# Top.net
KiCad netlist of a schematic drawn in Altium Designer
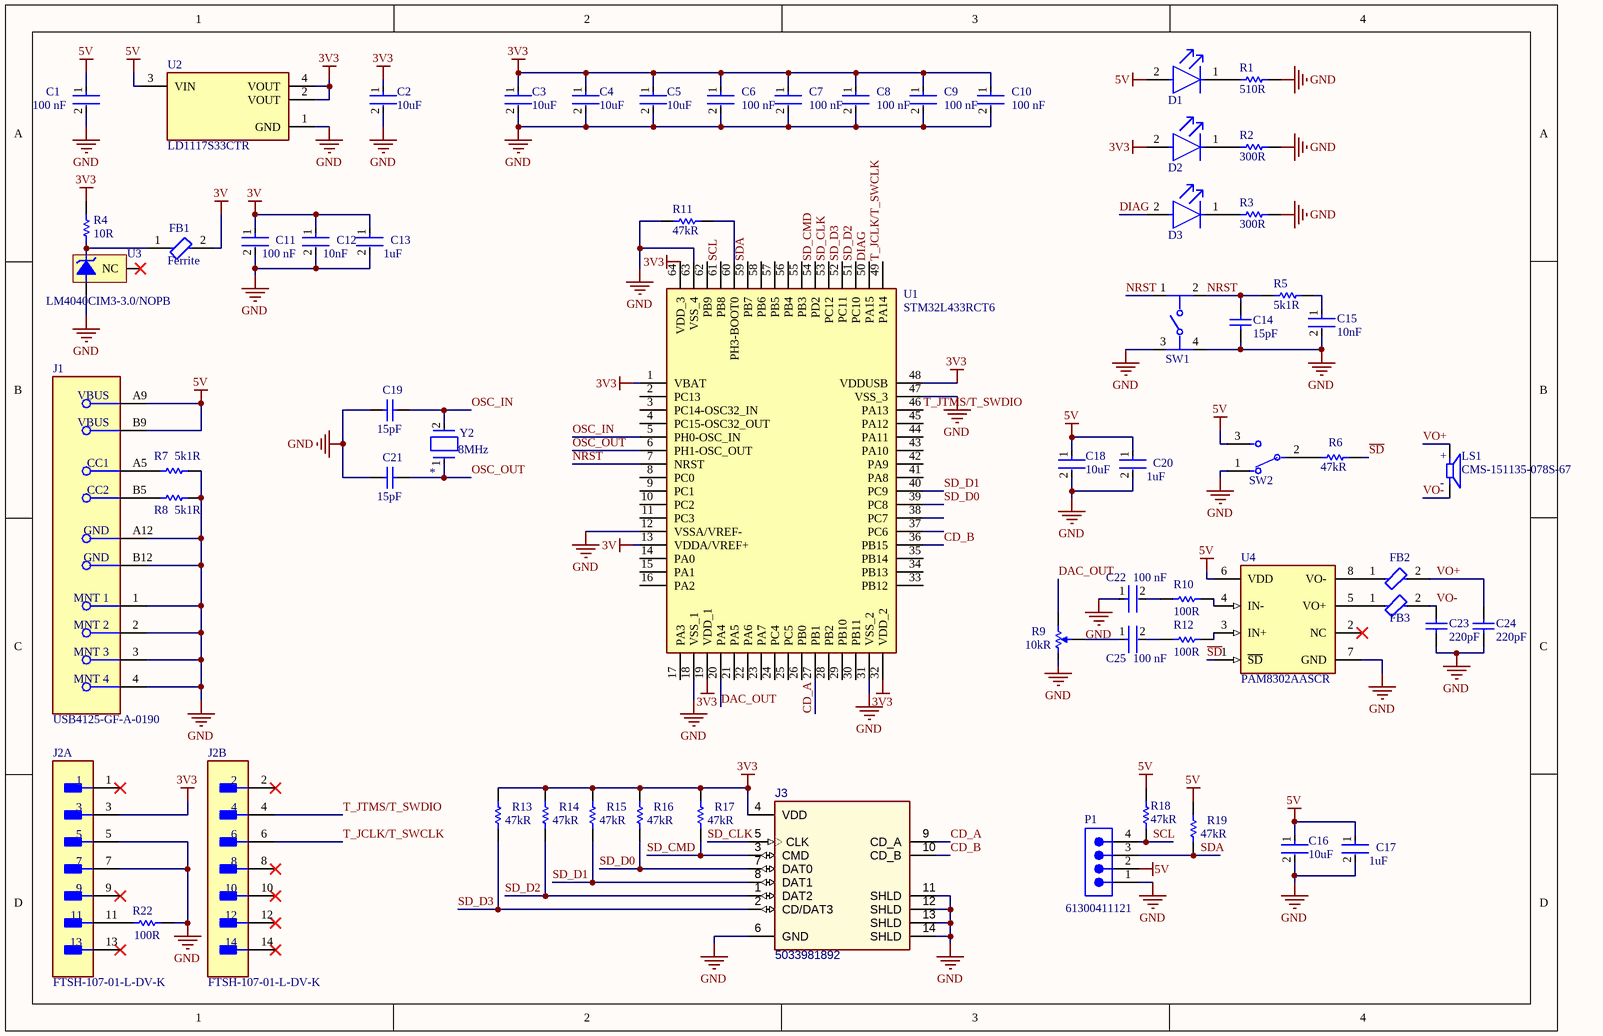
[diagram p0: Top.SchDoc]

(export (version "E")
  (design (tool "Eeschema 10.0.6"))
  (components
    (comp (ref "C1")
      (value "100 nF")
      (footprint "FP-CC0805-0_85-MFG")
      (description "CAP CER 0.1UF 16V X7R 0805")
      (fields
        (field (name "MANUFACTURER PART NUMBER") "CC0805KRX7R7BB104")
        (field (name "MANUFACTURER") "Yageo")
      )
      (libsource (lib "Altium Content Vault") (part "11868f565c42a9108669ba33697ecf6"))
    )
    (comp (ref "C2")
      (value "10uF")
      (footprint "FP-C0805C-DG-MFG")
      (description "CAP CER 10UF 10V X5R 0805")
      (fields (field (name "TOLERANCE") "10%") (field (name "MANUFACTURER PART NUMBER") "C0805C106K8PACTU"))
      (libsource (lib "Altium Content Vault") (part "11868f565c42a9108669ba33697ecf6"))
    )
    (comp (ref "C3")
      (value "10uF")
      (footprint "FP-C0805C-DG-MFG")
      (description "CAP CER 10UF 10V X5R 0805")
      (fields (field (name "TOLERANCE") "10%") (field (name "MANUFACTURER PART NUMBER") "C0805C106K8PACTU"))
      (libsource (lib "Altium Content Vault") (part "11868f565c42a9108669ba33697ecf6"))
    )
    (comp (ref "C4")
      (value "10uF")
      (footprint "FP-C0805C-DG-MFG")
      (description "CAP CER 10UF 10V X5R 0805")
      (fields (field (name "TOLERANCE") "10%") (field (name "MANUFACTURER PART NUMBER") "C0805C106K8PACTU"))
      (libsource (lib "Altium Content Vault") (part "11868f565c42a9108669ba33697ecf6"))
    )
    (comp (ref "C5")
      (value "10uF")
      (footprint "FP-C0805C-DG-MFG")
      (description "CAP CER 10UF 10V X5R 0805")
      (fields (field (name "TOLERANCE") "10%") (field (name "MANUFACTURER PART NUMBER") "C0805C106K8PACTU"))
      (libsource (lib "Altium Content Vault") (part "11868f565c42a9108669ba33697ecf6"))
    )
    (comp (ref "C6")
      (value "100 nF")
      (footprint "FP-CC0805-0_85-MFG")
      (description "CAP CER 0.1UF 16V X7R 0805")
      (fields
        (field (name "MANUFACTURER PART NUMBER") "CC0805KRX7R7BB104")
        (field (name "MANUFACTURER") "Yageo")
      )
      (libsource (lib "Altium Content Vault") (part "11868f565c42a9108669ba33697ecf6"))
    )
    (comp (ref "C7")
      (value "100 nF")
      (footprint "FP-CC0805-0_85-MFG")
      (description "CAP CER 0.1UF 16V X7R 0805")
      (fields
        (field (name "MANUFACTURER PART NUMBER") "CC0805KRX7R7BB104")
        (field (name "MANUFACTURER") "Yageo")
      )
      (libsource (lib "Altium Content Vault") (part "11868f565c42a9108669ba33697ecf6"))
    )
    (comp (ref "C8")
      (value "100 nF")
      (footprint "FP-CC0805-0_85-MFG")
      (description "CAP CER 0.1UF 16V X7R 0805")
      (fields
        (field (name "MANUFACTURER PART NUMBER") "CC0805KRX7R7BB104")
        (field (name "MANUFACTURER") "Yageo")
      )
      (libsource (lib "Altium Content Vault") (part "11868f565c42a9108669ba33697ecf6"))
    )
    (comp (ref "C9")
      (value "100 nF")
      (footprint "FP-CC0805-0_85-MFG")
      (description "CAP CER 0.1UF 16V X7R 0805")
      (fields
        (field (name "MANUFACTURER PART NUMBER") "CC0805KRX7R7BB104")
        (field (name "MANUFACTURER") "Yageo")
      )
      (libsource (lib "Altium Content Vault") (part "11868f565c42a9108669ba33697ecf6"))
    )
    (comp (ref "C10")
      (value "CC0805KRX7R7BB104")
      (footprint "FP-CC0805-0_85-MFG")
      (description "CAP CER 0.1UF 16V X7R 0805")
      (fields
        (field (name "MANUFACTURER") "Yageo")
        (field (name "OCTOPART") "https://octopart.com/cc0805krx7r7bb104-yageo-39467769")
        (field (name "CAPACITANCE") "100 nF")
      )
      (libsource (lib "Altium Content Vault") (part "11868f565c42a9108669ba33697ecf6"))
    )
    (comp (ref "C11")
      (value "C0805C103K2RACTU")
      (footprint "FP-C0805C-DN-MFG")
      (description "CAP CER 10000PF 200V X7R 0805")
      (fields
        (field (name "OCTOPART") "https://octopart.com/c0805c103k2ractu-kemet-9138347")
        (field (name "CAPACITANCE") "10nF")
        (field (name "TOLERANCE") "0.1")
      )
      (libsource (lib "Altium Content Vault") (part "b4654b650e69147ec39a6b967a45e02"))
    )
    (comp (ref "C12")
      (value "100 nF")
      (footprint "FP-CC0805-0_85-MFG")
      (description "CAP CER 0.1UF 16V X7R 0805")
      (fields
        (field (name "MANUFACTURER PART NUMBER") "CC0805KRX7R7BB104")
        (field (name "MANUFACTURER") "Yageo")
      )
      (libsource (lib "Altium Content Vault") (part "11868f565c42a9108669ba33697ecf6"))
    )
    (comp (ref "C13")
      (value "C2012X5R1E105K125AA")
      (footprint "FP-C2012-125-0_2-IPC_A")
      (description "Multilayer Ceramic Capacitors 1μF ±10% 25V X5R SMD 0805")
      (fields
        (field (name "VOLTAGE") "25V")
        (field (name "CAPACITANCE") "1uF")
        (field (name "TOLERANCE") "10%")
      )
      (libsource (lib "Altium Content Vault") (part "b4654b650e69147ec39a6b967a45e02"))
    )
    (comp (ref "C14")
      (value "15pF")
      (footprint "CAPC1508X91X25LL25T13")
      (fields
        (field (name "MANUFACTURER") "AVX Interconnect / Elco")
        (field (name "PART NUMBER") "06032U150GAT2A")
      )
      (libsource (lib "Altium Content Vault") (part "CAP"))
    )
    (comp (ref "C15")
      (value "C0805C103K2RACTU")
      (footprint "FP-C0805C-DN-MFG")
      (description "CAP CER 10000PF 200V X7R 0805")
      (fields
        (field (name "OCTOPART") "https://octopart.com/c0805c103k2ractu-kemet-9138347")
        (field (name "CAPACITANCE") "10nF")
        (field (name "TOLERANCE") "0.1")
      )
      (libsource (lib "Altium Content Vault") (part "b4654b650e69147ec39a6b967a45e02"))
    )
    (comp (ref "C16")
      (value "10uF")
      (footprint "FP-C0805C-DG-MFG")
      (description "CAP CER 10UF 10V X5R 0805")
      (fields (field (name "TOLERANCE") "10%") (field (name "MANUFACTURER PART NUMBER") "C0805C106K8PACTU"))
      (libsource (lib "Altium Content Vault") (part "11868f565c42a9108669ba33697ecf6"))
    )
    (comp (ref "C17")
      (value "C2012X5R1E105K125AA")
      (footprint "FP-C2012-125-0_2-IPC_A")
      (description "Multilayer Ceramic Capacitors 1μF ±10% 25V X5R SMD 0805")
      (fields
        (field (name "VOLTAGE") "25V")
        (field (name "CAPACITANCE") "1uF")
        (field (name "TOLERANCE") "10%")
      )
      (libsource (lib "Altium Content Vault") (part "b4654b650e69147ec39a6b967a45e02"))
    )
    (comp (ref "C18")
      (value "10uF")
      (footprint "FP-C0805C-DG-MFG")
      (description "CAP CER 10UF 10V X5R 0805")
      (fields (field (name "TOLERANCE") "10%") (field (name "MANUFACTURER PART NUMBER") "C0805C106K8PACTU"))
      (libsource (lib "Altium Content Vault") (part "11868f565c42a9108669ba33697ecf6"))
    )
    (comp (ref "C19")
      (value "15pF")
      (footprint "CAPC1508X91X25LL25T13")
      (fields
        (field (name "MANUFACTURER") "AVX Interconnect / Elco")
        (field (name "PART NUMBER") "06032U150GAT2A")
      )
      (libsource (lib "Altium Content Vault") (part "CAP"))
    )
    (comp (ref "C20")
      (value "C2012X5R1E105K125AA")
      (footprint "FP-C2012-125-0_2-IPC_A")
      (description "Multilayer Ceramic Capacitors 1μF ±10% 25V X5R SMD 0805")
      (fields
        (field (name "VOLTAGE") "25V")
        (field (name "CAPACITANCE") "1uF")
        (field (name "TOLERANCE") "10%")
      )
      (libsource (lib "Altium Content Vault") (part "b4654b650e69147ec39a6b967a45e02"))
    )
    (comp (ref "C21")
      (value "15pF")
      (footprint "CAPC1508X91X25LL25T13")
      (fields
        (field (name "MANUFACTURER") "AVX Interconnect / Elco")
        (field (name "PART NUMBER") "06032U150GAT2A")
      )
      (libsource (lib "Altium Content Vault") (part "CAP"))
    )
    (comp (ref "C22")
      (value "100 nF")
      (footprint "FP-CC0805-0_85-MFG")
      (description "CAP CER 0.1UF 16V X7R 0805")
      (fields
        (field (name "MANUFACTURER PART NUMBER") "CC0805KRX7R7BB104")
        (field (name "MANUFACTURER") "Yageo")
      )
      (libsource (lib "Altium Content Vault") (part "11868f565c42a9108669ba33697ecf6"))
    )
    (comp (ref "C23")
      (value "220pF")
      (footprint "CAPC2013X88X50ML20T25")
      (fields (field (name "MANUFACTURER") "Kemet") (field (name "PART NUMBER") "C0805C221K5RACTU"))
      (libsource (lib "Altium Content Vault") (part "CAP"))
    )
    (comp (ref "C24")
      (value "220pF")
      (footprint "CAPC2013X88X50ML20T25")
      (fields (field (name "MANUFACTURER") "Kemet") (field (name "PART NUMBER") "C0805C221K5RACTU"))
      (libsource (lib "Altium Content Vault") (part "CAP"))
    )
    (comp (ref "C25")
      (value "100 nF")
      (footprint "FP-CC0805-0_85-MFG")
      (description "CAP CER 0.1UF 16V X7R 0805")
      (fields
        (field (name "MANUFACTURER PART NUMBER") "CC0805KRX7R7BB104")
        (field (name "MANUFACTURER") "Yageo")
      )
      (libsource (lib "Altium Content Vault") (part "11868f565c42a9108669ba33697ecf6"))
    )
    (comp (ref "D1")
      (value "SML-LXT0805IW-TR")
      (footprint "FP-SML-LXT0805IW-TR-MFG")
      (description "LED RED DIFFUSED SMD")
      (libsource (lib "Altium Content Vault") (part "8706943c75ba83719d021d2fdc84c58"))
    )
    (comp (ref "D2")
      (value "SML-LXT0805IW-TR")
      (footprint "FP-SML-LXT0805IW-TR-MFG")
      (description "LED RED DIFFUSED SMD")
      (libsource (lib "Altium Content Vault") (part "8706943c75ba83719d021d2fdc84c58"))
    )
    (comp (ref "D3")
      (value "SML-LXT0805IW-TR")
      (footprint "FP-SML-LXT0805IW-TR-MFG")
      (description "LED RED DIFFUSED SMD")
      (libsource (lib "Altium Content Vault") (part "8706943c75ba83719d021d2fdc84c58"))
    )
    (comp (ref "FB1")
      (value "BLM21AG151SN1D")
      (footprint "FP-BLM21-0_2-t0_85-e0_5-MFG")
      (description "Chip Ferrite Bead, 0805, 150Ω @ 100MHz, 0.09Ω, 25%, 1A")
      (fields (field (name "CORE MATERIAL") "Ferrite") (field (name "TOLERANCE") "25%"))
      (libsource (lib "Altium Content Vault") (part "5f30dd21d616792df468990f7003faa"))
    )
    (comp (ref "FB2")
      (value "MMZ1608B121CTAH0")
      (footprint "FP-MMZ1608-0_6-MFG")
      (description "FERRITE BEAD 120 OHM 0603 1LN")
      (fields (field (name "TOLERANCE") "25%"))
      (libsource (lib "Altium Content Vault") (part "5f30dd21d616792df468990f7003faa"))
    )
    (comp (ref "FB3")
      (value "MMZ1608B121CTAH0")
      (footprint "FP-MMZ1608-0_6-MFG")
      (description "FERRITE BEAD 120 OHM 0603 1LN")
      (fields (field (name "TOLERANCE") "25%"))
      (libsource (lib "Altium Content Vault") (part "5f30dd21d616792df468990f7003faa"))
    )
    (comp (ref "J1")
      (value "USB4125-GF-A-0190")
      (footprint "FP-USB4125-GF-A-0190-MFG")
      (description "CONN RCPT TYPE C 6P SMD RA")
      (libsource (lib "Altium Content Vault") (part "a055484d46e58b234844902c9fd883a"))
    )
    (comp (ref "J2")
      (value "FTSH-107-01-L-DV-K")
      (footprint "FP-FTSH-107-01-L-DV-K-MFG")
      (description "CONN HEADER SMD 14POS 1.27MM")
      (libsource (lib "Altium Content Vault") (part "7644e1a88aa4da17242a9b8d8257442"))
    )
    (comp (ref "J3")
      (value "5033981892")
      (footprint "MOLX-5033981892_V")
      (libsource (lib "Open Robotics Drivetrain ELEC") (part "CMP-00040-6"))
    )
    (comp (ref "LS1")
      (value "CMS-151135-078S-67")
      (footprint "SPKR_CMS-151135-078S-67")
      (description "15 x 11 mm, Rectangular Frame, 0.7 W, 8 Ohm, Neodymium Magnet, Mylar Cone, Spring Contacts")
      (fields (field (name "MF") "{'manufacturer': u'CUI'}"))
      (libsource (lib "Open Robotics Drivetrain ELEC") (part "CMS-151135-078S-67"))
    )
    (comp (ref "P1")
      (value "61300411121")
      (footprint "61300411121")
      (libsource (lib "Altium Content Vault") (part "Header_Male_1R_04P"))
    )
    (comp (ref "R1")
      (value "510R")
      (footprint "RESC2013X60X35LL10T20")
      (fields (field (name "MANUFACTURER") "Yageo") (field (name "PART NUMBER") "RC0805JR-07510RL"))
      (libsource (lib "Altium Content Vault") (part "RES"))
    )
    (comp (ref "R2")
      (value "300R")
      (footprint "RESC2013X60X35LL10T20")
      (fields (field (name "MANUFACTURER") "Yageo") (field (name "PART NUMBER") "RC0805JR-07300RL"))
      (libsource (lib "Altium Content Vault") (part "RES"))
    )
    (comp (ref "R3")
      (value "300R")
      (footprint "RESC2013X60X35LL10T20")
      (fields (field (name "MANUFACTURER") "Yageo") (field (name "PART NUMBER") "RC0805JR-07300RL"))
      (libsource (lib "Altium Content Vault") (part "RES"))
    )
    (comp (ref "R4")
      (value "RC0805FR-0710RL")
      (footprint "RESC2013X60X35ML10T20")
      (description "Chip Resistor, 10 Ohm, +/- 1%, 0.125 W, -55 to 155 degC, 0805 (2012 Metric), RoHS, Tape and Reel")
      (fields
        (field (name "RESISTANCE") "10R")
        (field (name "MANUFACTURER") "Yageo")
        (field (name "TOLERANCE") "1%")
      )
      (libsource (lib "Altium Content Vault") (part "RES-2"))
    )
    (comp (ref "R5")
      (value "5k1R")
      (footprint "RESC2013X60X35ML10T20")
      (fields (field (name "PART NUMBER") "RC0805JR-075K1L") (field (name "MANUFACTURER") "Yageo"))
      (libsource (lib "Altium Content Vault") (part "RES"))
    )
    (comp (ref "R6")
      (value "47kR")
      (footprint "RESC2013X60X35NL10T20")
      (fields (field (name "MANUFACTURER") "Yageo") (field (name "PART NUMBER") "RC0805JR-1347KL"))
      (libsource (lib "Altium Content Vault") (part "RES"))
    )
    (comp (ref "R7")
      (value "5k1R")
      (footprint "RESC2013X60X35ML10T20")
      (fields (field (name "PART NUMBER") "RC0805JR-075K1L") (field (name "MANUFACTURER") "Yageo"))
      (libsource (lib "Altium Content Vault") (part "RES"))
    )
    (comp (ref "R8")
      (value "5k1R")
      (footprint "RESC2013X60X35ML10T20")
      (fields (field (name "PART NUMBER") "RC0805JR-075K1L") (field (name "MANUFACTURER") "Yageo"))
      (libsource (lib "Altium Content Vault") (part "RES"))
    )
    (comp (ref "R9")
      (value "TC33X-2-103E")
      (footprint "BOUR-TC33X-2_V")
      (description "Trimming Potentiometer, 10000 Ohm, -40 to 100 degC, 3-Pin SMD, RoHS, Tape and Reel")
      (fields
        (field (name "TOLERANCE") "25%")
        (field (name "RESISTANCE") "10kR")
        (field (name "MANUFACTURER") "Bourns")
      )
      (libsource (lib "Altium Content Vault") (part "RES-ADJ-3_A"))
    )
    (comp (ref "R10")
      (value "RC0805FR-07100RL")
      (footprint "RESC2013X60X35ML10T20")
      (description "Chip Resistor, 100 Ohm, +/-1%, 0.125 W, -55 to 155 degC, 0805 (2012 Metric), RoHS, Tape and Reel")
      (fields
        (field (name "RESISTANCE") "100R")
        (field (name "TOLERANCE") "1%")
        (field (name "MANUFACTURER") "Yageo")
      )
      (libsource (lib "Altium Content Vault") (part "RES-2"))
    )
    (comp (ref "R11")
      (value "47kR")
      (footprint "RESC2013X60X35NL10T20")
      (fields (field (name "MANUFACTURER") "Yageo") (field (name "PART NUMBER") "RC0805JR-1347KL"))
      (libsource (lib "Altium Content Vault") (part "RES"))
    )
    (comp (ref "R12")
      (value "RC0805FR-07100RL")
      (footprint "RESC2013X60X35ML10T20")
      (description "Chip Resistor, 100 Ohm, +/-1%, 0.125 W, -55 to 155 degC, 0805 (2012 Metric), RoHS, Tape and Reel")
      (fields
        (field (name "RESISTANCE") "100R")
        (field (name "TOLERANCE") "1%")
        (field (name "MANUFACTURER") "Yageo")
      )
      (libsource (lib "Altium Content Vault") (part "RES-2"))
    )
    (comp (ref "R13")
      (value "47kR")
      (footprint "RESC2013X60X35NL10T20")
      (fields (field (name "MANUFACTURER") "Yageo") (field (name "PART NUMBER") "RC0805JR-1347KL"))
      (libsource (lib "Altium Content Vault") (part "RES"))
    )
    (comp (ref "R14")
      (value "47kR")
      (footprint "RESC2013X60X35NL10T20")
      (fields (field (name "MANUFACTURER") "Yageo") (field (name "PART NUMBER") "RC0805JR-1347KL"))
      (libsource (lib "Altium Content Vault") (part "RES"))
    )
    (comp (ref "R15")
      (value "47kR")
      (footprint "RESC2013X60X35NL10T20")
      (fields (field (name "MANUFACTURER") "Yageo") (field (name "PART NUMBER") "RC0805JR-1347KL"))
      (libsource (lib "Altium Content Vault") (part "RES"))
    )
    (comp (ref "R16")
      (value "47kR")
      (footprint "RESC2013X60X35NL10T20")
      (fields (field (name "MANUFACTURER") "Yageo") (field (name "PART NUMBER") "RC0805JR-1347KL"))
      (libsource (lib "Altium Content Vault") (part "RES"))
    )
    (comp (ref "R17")
      (value "47kR")
      (footprint "RESC2013X60X35NL10T20")
      (fields (field (name "MANUFACTURER") "Yageo") (field (name "PART NUMBER") "RC0805JR-1347KL"))
      (libsource (lib "Altium Content Vault") (part "RES"))
    )
    (comp (ref "R18")
      (value "47kR")
      (footprint "RESC2013X60X35NL10T20")
      (fields (field (name "MANUFACTURER") "Yageo") (field (name "PART NUMBER") "RC0805JR-1347KL"))
      (libsource (lib "Altium Content Vault") (part "RES"))
    )
    (comp (ref "R19")
      (value "47kR")
      (footprint "RESC2013X60X35NL10T20")
      (fields (field (name "MANUFACTURER") "Yageo") (field (name "PART NUMBER") "RC0805JR-1347KL"))
      (libsource (lib "Altium Content Vault") (part "RES"))
    )
    (comp (ref "R22")
      (value "RC0805FR-07100RL")
      (footprint "RESC2013X60X35ML10T20")
      (description "Chip Resistor, 100 Ohm, +/-1%, 0.125 W, -55 to 155 degC, 0805 (2012 Metric), RoHS, Tape and Reel")
      (fields
        (field (name "RESISTANCE") "100R")
        (field (name "TOLERANCE") "1%")
        (field (name "MANUFACTURER") "Yageo")
      )
      (libsource (lib "Altium Content Vault") (part "RES-2"))
    )
    (comp (ref "SW1")
      (value "PTS645SM43SMTR92LFS")
      (footprint "FP-PTS645SM43SMTR92LFS-MFG")
      (description "SWITCH TACTILE SPST-NO 0.05A 12V")
      (libsource (lib "Altium Content Vault") (part "1adf0dd01260c80cf25a44bfd6b99ba"))
    )
    (comp (ref "SW2")
      (value "JS102011JCQN")
      (footprint "FP-JS102011JCQN-MFG")
      (description "SWITCH SLIDE SPDT 300MA 6V")
      (libsource (lib "Altium Content Vault") (part "52c419afdc2a387c7d548259a9aeefb"))
    )
    (comp (ref "U1")
      (value "STM32L433RCT6")
      (footprint "QFP50P1200X1200X160-64N")
      (description "STMICROELECTRONICS - STM32L433RCT6 - MCU, ARM CORTEX-M4, 80MHZ, LQFP-64")
      (fields (field (name "MOUSER PART NUMBER") "511-STM32L433RCT6"))
      (libsource (lib "Open Robotics Drivetrain ELEC") (part "STM32L433RCT6"))
    )
    (comp (ref "U2")
      (value "LD1117S33CTR")
      (footprint "FP-SOT-223-0046067_14-MFG")
      (description "IC REG LINEAR 3.3V 800MA SOT223")
      (libsource (lib "Altium Content Vault") (part "7818869c5c16ceab15634627166a29d"))
    )
    (comp (ref "U3")
      (value "LM4040CIM3-3.0/NOPB")
      (footprint "MF03A_N")
      (description "Precision Micropower Shunt Voltage Reference, 3-pin SOT-23, Pb-Free")
      (fields (field (name "MANUFACTURER") "National Semiconductor"))
      (libsource (lib "Altium Content Vault") (part "PM-REF-LM4040-SOT3"))
    )
    (comp (ref "U4")
      (value "PAM8302AASCR")
      (footprint "FP-MSOP-8-MFG")
      (description "IC AMP CLASS D MONO 2.5W 8MSOP")
      (fields
        (field (name "MANUFACTURER") "Diodes Inc.")
        (field (name "OCTOPART") "https://octopart.com/pam8302aascr-diodes+inc.-29030473")
      )
      (libsource (lib "Altium Content Vault") (part "918354b19a62d7b7ebf36b39aeda0fe"))
    )
    (comp (ref "Y2")
      (value "ABM3-8.000MHZ-B4Y-T")
      (footprint "FP-ABM3-MFG")
      (description "Crystal 8MHz ±30ppm 18pF SMD-2 5mm x 3.2mm")
      (fields (field (name "FREQUENCY") "8MHz") (field (name "PARAMETER 1") "*"))
      (libsource (lib "Altium Content Vault") (part "c23a69dc6c9e2f18f2079038eb95dd1"))
    )
  )
  (nets
    (net (code "1") (name "/CD_A") (class "Default")
      (node (ref "J3") (pin "9") (pinfunction "CD_A_9") (pintype "passive"))
      (node (ref "U1") (pin "27") (pinfunction "PB1_27") (pintype "passive"))
    )
    (net (code "2") (name "/CD_B") (class "Default")
      (node (ref "J3") (pin "10") (pinfunction "CD_B_10") (pintype "passive"))
      (node (ref "U1") (pin "36") (pinfunction "PB15_36") (pintype "passive"))
    )
    (net (code "3") (name "/DAC_OUT") (class "Default")
      (node (ref "R9") (pin "3") (pinfunction "3_3") (pintype "passive"))
      (node (ref "U1") (pin "20") (pinfunction "PA4_20") (pintype "passive"))
    )
    (net (code "4") (name "/DIAG") (class "Default")
      (node (ref "D3") (pin "2") (pinfunction "A_2") (pintype "passive"))
      (node (ref "U1") (pin "50") (pinfunction "PA15_50") (pintype "passive"))
    )
    (net (code "5") (name "/NRST") (class "Default")
      (node (ref "C14") (pin "2") (pinfunction "2_2") (pintype "passive"))
      (node (ref "R5") (pin "2") (pinfunction "2_2") (pintype "passive"))
      (node (ref "SW1") (pin "1") (pinfunction "1_1") (pintype "passive"))
      (node (ref "SW1") (pin "2") (pinfunction "2_2") (pintype "passive"))
      (node (ref "U1") (pin "7") (pinfunction "NRST_7") (pintype "passive"))
    )
    (net (code "6") (name "/OSC_IN") (class "Default")
      (node (ref "C19") (pin "2") (pinfunction "2_2") (pintype "passive"))
      (node (ref "U1") (pin "5") (pinfunction "PH0-OSC_IN_5") (pintype "passive"))
      (node (ref "Y2") (pin "2") (pinfunction "2_2") (pintype "passive"))
    )
    (net (code "7") (name "/OSC_OUT") (class "Default")
      (node (ref "C21") (pin "2") (pinfunction "2_2") (pintype "passive"))
      (node (ref "U1") (pin "6") (pinfunction "PH1-OSC_OUT_6") (pintype "passive"))
      (node (ref "Y2") (pin "1") (pinfunction "1_1") (pintype "passive"))
    )
    (net (code "8") (name "/SCL") (class "Default")
      (node (ref "P1") (pin "4") (pinfunction "4_4") (pintype "passive"))
      (node (ref "R18") (pin "1") (pinfunction "1_1") (pintype "passive"))
      (node (ref "U1") (pin "61") (pinfunction "PB8_61") (pintype "passive"))
    )
    (net (code "9") (name "/SDA") (class "Default")
      (node (ref "P1") (pin "3") (pinfunction "3_3") (pintype "passive"))
      (node (ref "R19") (pin "2") (pinfunction "2_2") (pintype "passive"))
      (node (ref "U1") (pin "59") (pinfunction "PB7_59") (pintype "passive"))
    )
    (net (code "10") (name "/SD_CLK") (class "Default")
      (node (ref "J3") (pin "5") (pinfunction "CLK_5") (pintype "input"))
      (node (ref "U1") (pin "53") (pinfunction "PC12_53") (pintype "passive"))
    )
    (net (code "11") (name "/SD_CMD") (class "Default")
      (node (ref "J3") (pin "3") (pinfunction "CMD_3") (pintype "bidirectional"))
      (node (ref "R17") (pin "2") (pinfunction "2_2") (pintype "passive"))
      (node (ref "U1") (pin "54") (pinfunction "PD2_54") (pintype "passive"))
    )
    (net (code "12") (name "/SD_D0") (class "Default")
      (node (ref "J3") (pin "7") (pinfunction "DAT0_7") (pintype "bidirectional"))
      (node (ref "R16") (pin "2") (pinfunction "2_2") (pintype "passive"))
      (node (ref "U1") (pin "39") (pinfunction "PC8_39") (pintype "passive"))
    )
    (net (code "13") (name "/SD_D1") (class "Default")
      (node (ref "J3") (pin "8") (pinfunction "DAT1_8") (pintype "bidirectional"))
      (node (ref "R15") (pin "2") (pinfunction "2_2") (pintype "passive"))
      (node (ref "U1") (pin "40") (pinfunction "PC9_40") (pintype "passive"))
    )
    (net (code "14") (name "/SD_D2") (class "Default")
      (node (ref "J3") (pin "1") (pinfunction "DAT2_1") (pintype "bidirectional"))
      (node (ref "R14") (pin "2") (pinfunction "2_2") (pintype "passive"))
      (node (ref "U1") (pin "51") (pinfunction "PC10_51") (pintype "passive"))
    )
    (net (code "15") (name "/SD_D3") (class "Default")
      (node (ref "J3") (pin "2") (pinfunction "CD/DAT3_2") (pintype "bidirectional"))
      (node (ref "R13") (pin "2") (pinfunction "2_2") (pintype "passive"))
      (node (ref "U1") (pin "52") (pinfunction "PC11_52") (pintype "passive"))
    )
    (net (code "16") (name "/T_JCLK{slash}T_SWCLK") (class "Default")
      (node (ref "J2") (pin "6") (pinfunction "6_6") (pintype "passive"))
      (node (ref "U1") (pin "49") (pinfunction "PA14_49") (pintype "passive"))
    )
    (net (code "17") (name "/T_JTMS{slash}T_SWDIO") (class "Default")
      (node (ref "J2") (pin "4") (pinfunction "4_4") (pintype "passive"))
      (node (ref "U1") (pin "46") (pinfunction "PA13_46") (pintype "passive"))
    )
    (net (code "18") (name "/VO+") (class "Default")
      (node (ref "C24") (pin "2") (pinfunction "2_2") (pintype "passive"))
      (node (ref "FB2") (pin "2") (pinfunction "2_2") (pintype "passive"))
      (node (ref "LS1") (pin "P") (pinfunction "P_P") (pintype "passive"))
    )
    (net (code "19") (name "/VO-") (class "Default")
      (node (ref "C23") (pin "2") (pinfunction "2_2") (pintype "passive"))
      (node (ref "FB3") (pin "2") (pinfunction "2_2") (pintype "passive"))
      (node (ref "LS1") (pin "M") (pinfunction "M_M") (pintype "passive"))
    )
    (net (code "20") (name "/~{SD}") (class "Default")
      (node (ref "R6") (pin "1") (pinfunction "1_1") (pintype "passive"))
      (node (ref "U4") (pin "1") (pinfunction "~{SD}_1") (pintype "input"))
    )
    (net (code "21") (name "3V") (class "Default")
      (node (ref "C11") (pin "1") (pinfunction "1_1") (pintype "passive"))
      (node (ref "C12") (pin "1") (pinfunction "1_1") (pintype "passive"))
      (node (ref "C13") (pin "1") (pinfunction "1_1") (pintype "passive"))
      (node (ref "FB1") (pin "2") (pinfunction "2_2") (pintype "passive"))
      (node (ref "U1") (pin "13") (pinfunction "VDDA/VREF+_13") (pintype "passive"))
    )
    (net (code "22") (name "3V3") (class "Default")
      (node (ref "C10") (pin "1") (pinfunction "1_1") (pintype "passive"))
      (node (ref "C2") (pin "1") (pinfunction "1_1") (pintype "passive"))
      (node (ref "C3") (pin "1") (pinfunction "1_1") (pintype "passive"))
      (node (ref "C4") (pin "1") (pinfunction "1_1") (pintype "passive"))
      (node (ref "C5") (pin "1") (pinfunction "1_1") (pintype "passive"))
      (node (ref "C6") (pin "1") (pinfunction "1_1") (pintype "passive"))
      (node (ref "C7") (pin "1") (pinfunction "1_1") (pintype "passive"))
      (node (ref "C8") (pin "1") (pinfunction "1_1") (pintype "passive"))
      (node (ref "C9") (pin "1") (pinfunction "1_1") (pintype "passive"))
      (node (ref "D2") (pin "2") (pinfunction "A_2") (pintype "passive"))
      (node (ref "J2") (pin "3") (pinfunction "3_3") (pintype "passive"))
      (node (ref "J3") (pin "4") (pinfunction "VDD_4") (pintype "power_in"))
      (node (ref "R13") (pin "1") (pinfunction "1_1") (pintype "passive"))
      (node (ref "R14") (pin "1") (pinfunction "1_1") (pintype "passive"))
      (node (ref "R15") (pin "1") (pinfunction "1_1") (pintype "passive"))
      (node (ref "R16") (pin "1") (pinfunction "1_1") (pintype "passive"))
      (node (ref "R17") (pin "1") (pinfunction "1_1") (pintype "passive"))
      (node (ref "R4") (pin "2") (pinfunction "2_2") (pintype "passive"))
      (node (ref "U1") (pin "1") (pinfunction "VBAT_1") (pintype "passive"))
      (node (ref "U1") (pin "19") (pinfunction "VDD_1_19") (pintype "passive"))
      (node (ref "U1") (pin "32") (pinfunction "VDD_2_32") (pintype "passive"))
      (node (ref "U1") (pin "48") (pinfunction "VDDUSB_48") (pintype "passive"))
      (node (ref "U1") (pin "64") (pinfunction "VDD_3_64") (pintype "passive"))
      (node (ref "U2") (pin "2") (pinfunction "VOUT_2") (pintype "power_in"))
      (node (ref "U2") (pin "4") (pinfunction "VOUT_4") (pintype "power_in"))
    )
    (net (code "23") (name "5V") (class "Default")
      (node (ref "C1") (pin "1") (pinfunction "1_1") (pintype "passive"))
      (node (ref "C16") (pin "1") (pinfunction "1_1") (pintype "passive"))
      (node (ref "C17") (pin "1") (pinfunction "1_1") (pintype "passive"))
      (node (ref "C18") (pin "1") (pinfunction "1_1") (pintype "passive"))
      (node (ref "C20") (pin "1") (pinfunction "1_1") (pintype "passive"))
      (node (ref "D1") (pin "2") (pinfunction "A_2") (pintype "passive"))
      (node (ref "J1") (pin "A9") (pinfunction "VBUS_A9") (pintype "passive"))
      (node (ref "J1") (pin "B9") (pinfunction "VBUS_B9") (pintype "passive"))
      (node (ref "P1") (pin "2") (pinfunction "2_2") (pintype "passive"))
      (node (ref "R18") (pin "2") (pinfunction "2_2") (pintype "passive"))
      (node (ref "R19") (pin "1") (pinfunction "1_1") (pintype "passive"))
      (node (ref "SW2") (pin "3") (pinfunction "3_3") (pintype "passive"))
      (node (ref "U2") (pin "3") (pinfunction "VIN_3") (pintype "power_in"))
      (node (ref "U4") (pin "6") (pinfunction "VDD_6") (pintype "power_in"))
    )
    (net (code "24") (name "GND") (class "Default")
      (node (ref "C1") (pin "2") (pinfunction "2_2") (pintype "passive"))
      (node (ref "C10") (pin "2") (pinfunction "2_2") (pintype "passive"))
      (node (ref "C11") (pin "2") (pinfunction "2_2") (pintype "passive"))
      (node (ref "C12") (pin "2") (pinfunction "2_2") (pintype "passive"))
      (node (ref "C13") (pin "2") (pinfunction "2_2") (pintype "passive"))
      (node (ref "C14") (pin "1") (pinfunction "1_1") (pintype "passive"))
      (node (ref "C15") (pin "2") (pinfunction "2_2") (pintype "passive"))
      (node (ref "C16") (pin "2") (pinfunction "2_2") (pintype "passive"))
      (node (ref "C17") (pin "2") (pinfunction "2_2") (pintype "passive"))
      (node (ref "C18") (pin "2") (pinfunction "2_2") (pintype "passive"))
      (node (ref "C19") (pin "1") (pinfunction "1_1") (pintype "passive"))
      (node (ref "C2") (pin "2") (pinfunction "2_2") (pintype "passive"))
      (node (ref "C20") (pin "2") (pinfunction "2_2") (pintype "passive"))
      (node (ref "C21") (pin "1") (pinfunction "1_1") (pintype "passive"))
      (node (ref "C22") (pin "1") (pinfunction "1_1") (pintype "passive"))
      (node (ref "C23") (pin "1") (pinfunction "1_1") (pintype "passive"))
      (node (ref "C24") (pin "1") (pinfunction "1_1") (pintype "passive"))
      (node (ref "C3") (pin "2") (pinfunction "2_2") (pintype "passive"))
      (node (ref "C4") (pin "2") (pinfunction "2_2") (pintype "passive"))
      (node (ref "C5") (pin "2") (pinfunction "2_2") (pintype "passive"))
      (node (ref "C6") (pin "2") (pinfunction "2_2") (pintype "passive"))
      (node (ref "C7") (pin "2") (pinfunction "2_2") (pintype "passive"))
      (node (ref "C8") (pin "2") (pinfunction "2_2") (pintype "passive"))
      (node (ref "C9") (pin "2") (pinfunction "2_2") (pintype "passive"))
      (node (ref "J1") (pin "1") (pinfunction "MNT_1_1") (pintype "passive"))
      (node (ref "J1") (pin "2") (pinfunction "MNT_2_2") (pintype "passive"))
      (node (ref "J1") (pin "3") (pinfunction "MNT_3_3") (pintype "passive"))
      (node (ref "J1") (pin "4") (pinfunction "MNT_4_4") (pintype "passive"))
      (node (ref "J1") (pin "A12") (pinfunction "GND_A12") (pintype "passive"))
      (node (ref "J1") (pin "B12") (pinfunction "GND_B12") (pintype "passive"))
      (node (ref "J2") (pin "5") (pinfunction "5_5") (pintype "passive"))
      (node (ref "J2") (pin "7") (pinfunction "7_7") (pintype "passive"))
      (node (ref "J3") (pin "11") (pinfunction "SHLD_11") (pintype "passive"))
      (node (ref "J3") (pin "12") (pinfunction "SHLD_12") (pintype "passive"))
      (node (ref "J3") (pin "13") (pinfunction "SHLD_13") (pintype "passive"))
      (node (ref "J3") (pin "14") (pinfunction "SHLD_14") (pintype "passive"))
      (node (ref "J3") (pin "6") (pinfunction "GND_6") (pintype "passive"))
      (node (ref "P1") (pin "1") (pinfunction "1_1") (pintype "passive"))
      (node (ref "R1") (pin "1") (pinfunction "1_1") (pintype "passive"))
      (node (ref "R11") (pin "1") (pinfunction "1_1") (pintype "passive"))
      (node (ref "R2") (pin "1") (pinfunction "1_1") (pintype "passive"))
      (node (ref "R22") (pin "2") (pinfunction "2_2") (pintype "passive"))
      (node (ref "R3") (pin "1") (pinfunction "1_1") (pintype "passive"))
      (node (ref "R7") (pin "1") (pinfunction "1_1") (pintype "passive"))
      (node (ref "R8") (pin "1") (pinfunction "1_1") (pintype "passive"))
      (node (ref "R9") (pin "1") (pinfunction "1_1") (pintype "passive"))
      (node (ref "SW1") (pin "3") (pinfunction "3_3") (pintype "passive"))
      (node (ref "SW1") (pin "4") (pinfunction "4_4") (pintype "passive"))
      (node (ref "SW2") (pin "1") (pinfunction "1_1") (pintype "passive"))
      (node (ref "U1") (pin "12") (pinfunction "VSSA/VREF-_12") (pintype "passive"))
      (node (ref "U1") (pin "18") (pinfunction "VSS_1_18") (pintype "passive"))
      (node (ref "U1") (pin "31") (pinfunction "VSS_2_31") (pintype "passive"))
      (node (ref "U1") (pin "47") (pinfunction "VSS_3_47") (pintype "passive"))
      (node (ref "U1") (pin "63") (pinfunction "VSS_4_63") (pintype "passive"))
      (node (ref "U2") (pin "1") (pinfunction "GND_1") (pintype "power_in"))
      (node (ref "U3") (pin "2") (pinfunction "-V_2") (pintype "passive"))
      (node (ref "U4") (pin "7") (pinfunction "GND_7") (pintype "power_in"))
    )
    (net (code "25") (name "Net-(C15-Pad1)") (class "Default")
      (node (ref "C15") (pin "1") (pinfunction "1_1") (pintype "passive"))
      (node (ref "R5") (pin "1") (pinfunction "1_1") (pintype "passive"))
    )
    (net (code "26") (name "Net-(C22-Pad2)") (class "Default")
      (node (ref "C22") (pin "2") (pinfunction "2_2") (pintype "passive"))
      (node (ref "R10") (pin "1") (pinfunction "1_1") (pintype "passive"))
    )
    (net (code "27") (name "Net-(C25-Pad1)") (class "Default")
      (node (ref "C25") (pin "1") (pinfunction "1_1") (pintype "passive"))
      (node (ref "R9") (pin "2") (pinfunction "2_2") (pintype "passive"))
    )
    (net (code "28") (name "Net-(C25-Pad2)") (class "Default")
      (node (ref "C25") (pin "2") (pinfunction "2_2") (pintype "passive"))
      (node (ref "R12") (pin "1") (pinfunction "1_1") (pintype "passive"))
    )
    (net (code "29") (name "Net-(D1-C)") (class "Default")
      (node (ref "D1") (pin "1") (pinfunction "C_1") (pintype "passive"))
      (node (ref "R1") (pin "2") (pinfunction "2_2") (pintype "passive"))
    )
    (net (code "30") (name "Net-(D2-C)") (class "Default")
      (node (ref "D2") (pin "1") (pinfunction "C_1") (pintype "passive"))
      (node (ref "R2") (pin "2") (pinfunction "2_2") (pintype "passive"))
    )
    (net (code "31") (name "Net-(D3-C)") (class "Default")
      (node (ref "D3") (pin "1") (pinfunction "C_1") (pintype "passive"))
      (node (ref "R3") (pin "2") (pinfunction "2_2") (pintype "passive"))
    )
    (net (code "32") (name "Net-(J1-CC1)") (class "Default")
      (node (ref "J1") (pin "A5") (pinfunction "CC1_A5") (pintype "passive"))
      (node (ref "R7") (pin "2") (pinfunction "2_2") (pintype "passive"))
    )
    (net (code "33") (name "Net-(J1-CC2)") (class "Default")
      (node (ref "J1") (pin "B5") (pinfunction "CC2_B5") (pintype "passive"))
      (node (ref "R8") (pin "2") (pinfunction "2_2") (pintype "passive"))
    )
    (net (code "34") (name "Net-(J2-Pad11)") (class "Default")
      (node (ref "J2") (pin "11") (pinfunction "11_11") (pintype "passive"))
      (node (ref "R22") (pin "1") (pinfunction "1_1") (pintype "passive"))
    )
    (net (code "35") (name "Net-(R6-Pad2)") (class "Default")
      (node (ref "R6") (pin "2") (pinfunction "2_2") (pintype "passive"))
      (node (ref "SW2") (pin "2") (pinfunction "2_2") (pintype "passive"))
    )
    (net (code "36") (name "Net-(U1-PH3-BOOT0)") (class "Default")
      (node (ref "R11") (pin "2") (pinfunction "2_2") (pintype "passive"))
      (node (ref "U1") (pin "60") (pinfunction "PH3-BOOT0_60") (pintype "passive"))
    )
    (net (code "37") (name "Net-(U3-+V)") (class "Default")
      (node (ref "FB1") (pin "1") (pinfunction "1_1") (pintype "passive"))
      (node (ref "R4") (pin "1") (pinfunction "1_1") (pintype "passive"))
      (node (ref "U3") (pin "1") (pinfunction "+V_1") (pintype "passive"))
    )
    (net (code "38") (name "Net-(U4-IN+)") (class "Default")
      (node (ref "R12") (pin "2") (pinfunction "2_2") (pintype "passive"))
      (node (ref "U4") (pin "3") (pinfunction "IN+_3") (pintype "input"))
    )
    (net (code "39") (name "Net-(U4-IN-)") (class "Default")
      (node (ref "R10") (pin "2") (pinfunction "2_2") (pintype "passive"))
      (node (ref "U4") (pin "4") (pinfunction "IN-_4") (pintype "input"))
    )
    (net (code "40") (name "Net-(U4-VO+)") (class "Default")
      (node (ref "FB3") (pin "1") (pinfunction "1_1") (pintype "passive"))
      (node (ref "U4") (pin "5") (pinfunction "VO+_5") (pintype "power_in"))
    )
    (net (code "41") (name "Net-(U4-VO-)") (class "Default")
      (node (ref "FB2") (pin "1") (pinfunction "1_1") (pintype "passive"))
      (node (ref "U4") (pin "8") (pinfunction "VO-_8") (pintype "power_in"))
    )
    (net (code "42") (name "unconnected-(J2-Pad1)") (class "Default")
      (node (ref "J2") (pin "1") (pinfunction "1_1") (pintype "passive+no_connect"))
    )
    (net (code "43") (name "unconnected-(J2-Pad2)") (class "Default")
      (node (ref "J2") (pin "2") (pinfunction "2_2") (pintype "passive+no_connect"))
    )
    (net (code "44") (name "unconnected-(J2-Pad8)") (class "Default")
      (node (ref "J2") (pin "8") (pinfunction "8_8") (pintype "passive+no_connect"))
    )
    (net (code "45") (name "unconnected-(J2-Pad9)") (class "Default")
      (node (ref "J2") (pin "9") (pinfunction "9_9") (pintype "passive+no_connect"))
    )
    (net (code "46") (name "unconnected-(J2-Pad10)") (class "Default")
      (node (ref "J2") (pin "10") (pinfunction "10_10") (pintype "passive+no_connect"))
    )
    (net (code "47") (name "unconnected-(J2-Pad12)") (class "Default")
      (node (ref "J2") (pin "12") (pinfunction "12_12") (pintype "passive+no_connect"))
    )
    (net (code "48") (name "unconnected-(J2-Pad13)") (class "Default")
      (node (ref "J2") (pin "13") (pinfunction "13_13") (pintype "passive+no_connect"))
    )
    (net (code "49") (name "unconnected-(J2-Pad14)") (class "Default")
      (node (ref "J2") (pin "14") (pinfunction "14_14") (pintype "passive+no_connect"))
    )
    (net (code "50") (name "unconnected-(U1-PA0-Pad14)") (class "Default")
      (node (ref "U1") (pin "14") (pinfunction "PA0_14") (pintype "passive"))
    )
    (net (code "51") (name "unconnected-(U1-PA1-Pad15)") (class "Default")
      (node (ref "U1") (pin "15") (pinfunction "PA1_15") (pintype "passive"))
    )
    (net (code "52") (name "unconnected-(U1-PA2-Pad16)") (class "Default")
      (node (ref "U1") (pin "16") (pinfunction "PA2_16") (pintype "passive"))
    )
    (net (code "53") (name "unconnected-(U1-PA3-Pad17)") (class "Default")
      (node (ref "U1") (pin "17") (pinfunction "PA3_17") (pintype "passive"))
    )
    (net (code "54") (name "unconnected-(U1-PA5-Pad21)") (class "Default")
      (node (ref "U1") (pin "21") (pinfunction "PA5_21") (pintype "passive"))
    )
    (net (code "55") (name "unconnected-(U1-PA6-Pad22)") (class "Default")
      (node (ref "U1") (pin "22") (pinfunction "PA6_22") (pintype "passive"))
    )
    (net (code "56") (name "unconnected-(U1-PA7-Pad23)") (class "Default")
      (node (ref "U1") (pin "23") (pinfunction "PA7_23") (pintype "passive"))
    )
    (net (code "57") (name "unconnected-(U1-PA8-Pad41)") (class "Default")
      (node (ref "U1") (pin "41") (pinfunction "PA8_41") (pintype "passive"))
    )
    (net (code "58") (name "unconnected-(U1-PA9-Pad42)") (class "Default")
      (node (ref "U1") (pin "42") (pinfunction "PA9_42") (pintype "passive"))
    )
    (net (code "59") (name "unconnected-(U1-PA10-Pad43)") (class "Default")
      (node (ref "U1") (pin "43") (pinfunction "PA10_43") (pintype "passive"))
    )
    (net (code "60") (name "unconnected-(U1-PA11-Pad44)") (class "Default")
      (node (ref "U1") (pin "44") (pinfunction "PA11_44") (pintype "passive"))
    )
    (net (code "61") (name "unconnected-(U1-PA12-Pad45)") (class "Default")
      (node (ref "U1") (pin "45") (pinfunction "PA12_45") (pintype "passive"))
    )
    (net (code "62") (name "unconnected-(U1-PB0-Pad26)") (class "Default")
      (node (ref "U1") (pin "26") (pinfunction "PB0_26") (pintype "passive"))
    )
    (net (code "63") (name "unconnected-(U1-PB2-Pad28)") (class "Default")
      (node (ref "U1") (pin "28") (pinfunction "PB2_28") (pintype "passive"))
    )
    (net (code "64") (name "unconnected-(U1-PB3-Pad55)") (class "Default")
      (node (ref "U1") (pin "55") (pinfunction "PB3_55") (pintype "passive"))
    )
    (net (code "65") (name "unconnected-(U1-PB4-Pad56)") (class "Default")
      (node (ref "U1") (pin "56") (pinfunction "PB4_56") (pintype "passive"))
    )
    (net (code "66") (name "unconnected-(U1-PB5-Pad57)") (class "Default")
      (node (ref "U1") (pin "57") (pinfunction "PB5_57") (pintype "passive"))
    )
    (net (code "67") (name "unconnected-(U1-PB6-Pad58)") (class "Default")
      (node (ref "U1") (pin "58") (pinfunction "PB6_58") (pintype "passive"))
    )
    (net (code "68") (name "unconnected-(U1-PB9-Pad62)") (class "Default")
      (node (ref "U1") (pin "62") (pinfunction "PB9_62") (pintype "passive"))
    )
    (net (code "69") (name "unconnected-(U1-PB10-Pad29)") (class "Default")
      (node (ref "U1") (pin "29") (pinfunction "PB10_29") (pintype "passive"))
    )
    (net (code "70") (name "unconnected-(U1-PB11-Pad30)") (class "Default")
      (node (ref "U1") (pin "30") (pinfunction "PB11_30") (pintype "passive"))
    )
    (net (code "71") (name "unconnected-(U1-PB12-Pad33)") (class "Default")
      (node (ref "U1") (pin "33") (pinfunction "PB12_33") (pintype "passive"))
    )
    (net (code "72") (name "unconnected-(U1-PB13-Pad34)") (class "Default")
      (node (ref "U1") (pin "34") (pinfunction "PB13_34") (pintype "passive"))
    )
    (net (code "73") (name "unconnected-(U1-PB14-Pad35)") (class "Default")
      (node (ref "U1") (pin "35") (pinfunction "PB14_35") (pintype "passive"))
    )
    (net (code "74") (name "unconnected-(U1-PC0-Pad8)") (class "Default")
      (node (ref "U1") (pin "8") (pinfunction "PC0_8") (pintype "passive"))
    )
    (net (code "75") (name "unconnected-(U1-PC1-Pad9)") (class "Default")
      (node (ref "U1") (pin "9") (pinfunction "PC1_9") (pintype "passive"))
    )
    (net (code "76") (name "unconnected-(U1-PC2-Pad10)") (class "Default")
      (node (ref "U1") (pin "10") (pinfunction "PC2_10") (pintype "passive"))
    )
    (net (code "77") (name "unconnected-(U1-PC3-Pad11)") (class "Default")
      (node (ref "U1") (pin "11") (pinfunction "PC3_11") (pintype "passive"))
    )
    (net (code "78") (name "unconnected-(U1-PC4-Pad24)") (class "Default")
      (node (ref "U1") (pin "24") (pinfunction "PC4_24") (pintype "passive"))
    )
    (net (code "79") (name "unconnected-(U1-PC5-Pad25)") (class "Default")
      (node (ref "U1") (pin "25") (pinfunction "PC5_25") (pintype "passive"))
    )
    (net (code "80") (name "unconnected-(U1-PC6-Pad37)") (class "Default")
      (node (ref "U1") (pin "37") (pinfunction "PC6_37") (pintype "passive"))
    )
    (net (code "81") (name "unconnected-(U1-PC7-Pad38)") (class "Default")
      (node (ref "U1") (pin "38") (pinfunction "PC7_38") (pintype "passive"))
    )
    (net (code "82") (name "unconnected-(U1-PC13-Pad2)") (class "Default")
      (node (ref "U1") (pin "2") (pinfunction "PC13_2") (pintype "passive"))
    )
    (net (code "83") (name "unconnected-(U1-PC14-OSC32_IN-Pad3)") (class "Default")
      (node (ref "U1") (pin "3") (pinfunction "PC14-OSC32_IN_3") (pintype "passive"))
    )
    (net (code "84") (name "unconnected-(U1-PC15-OSC32_OUT-Pad4)") (class "Default")
      (node (ref "U1") (pin "4") (pinfunction "PC15-OSC32_OUT_4") (pintype "passive"))
    )
    (net (code "85") (name "unconnected-(U3-NC-Pad3)") (class "Default")
      (node (ref "U3") (pin "3") (pinfunction "NC_3") (pintype "passive+no_connect"))
    )
    (net (code "86") (name "unconnected-(U4-NC-Pad2)") (class "Default")
      (node (ref "U4") (pin "2") (pinfunction "NC_2") (pintype "passive+no_connect"))
    )
  )
)
